# Actuators.net
KiCad netlist of a schematic drawn in Altium Designer
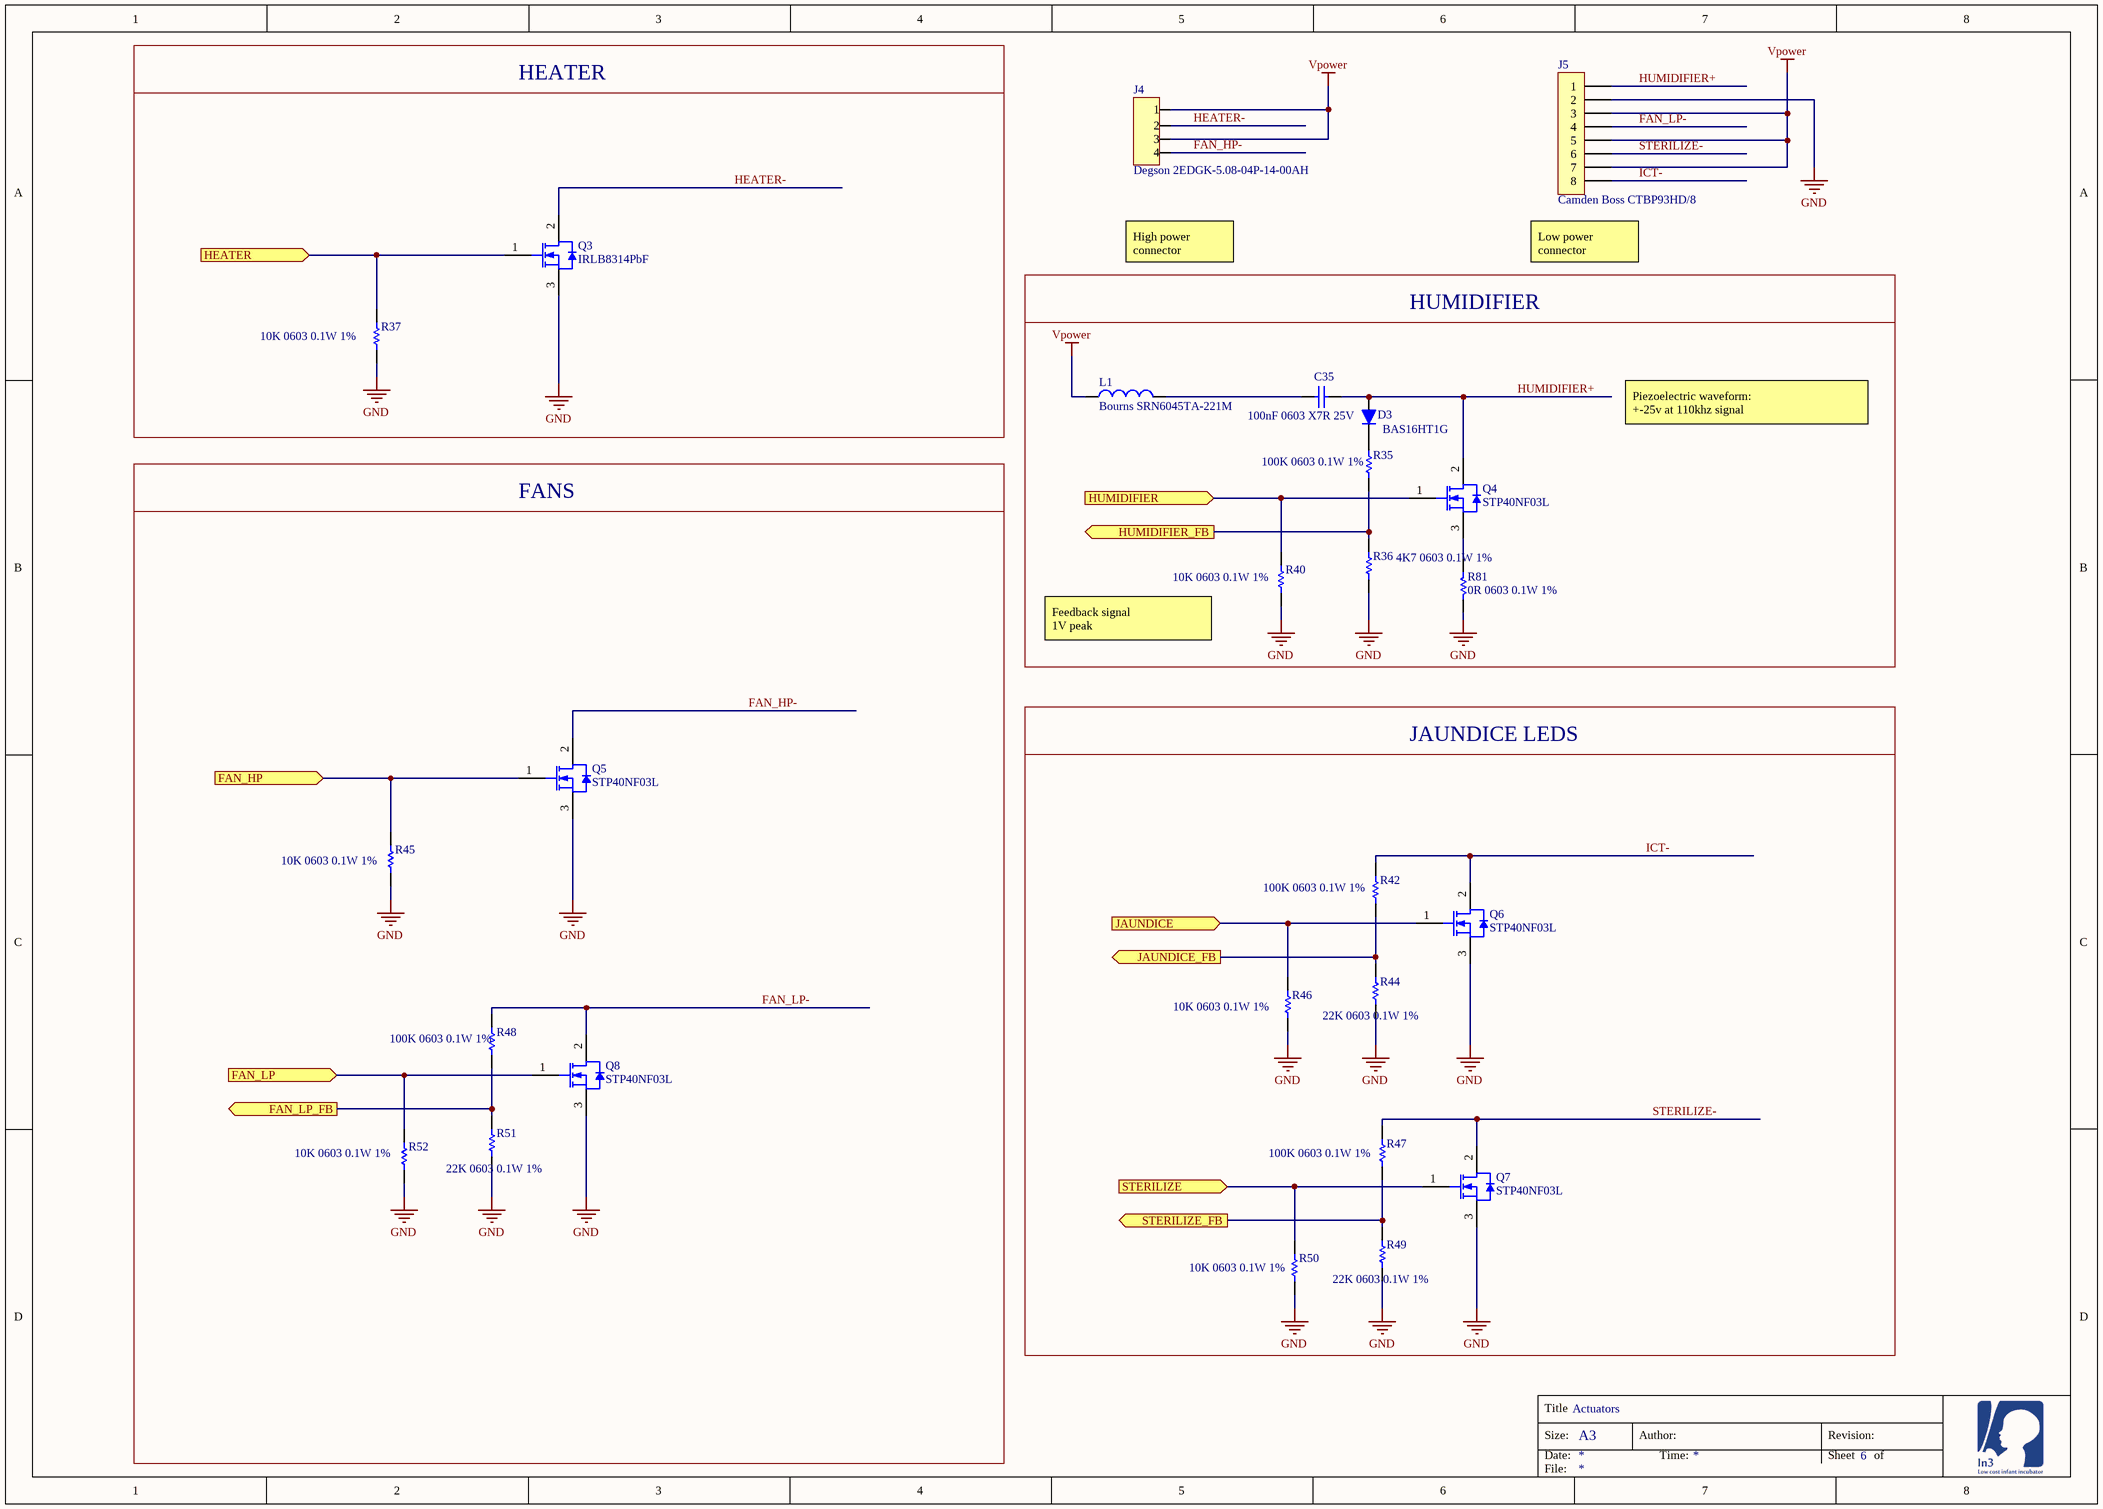
[diagram p0: Actuators.SchDoc]

(export (version "E")
  (design (tool "Eeschema 10.0.6"))
  (components
    (comp (ref "C35")
      (value "100nF 0603 X7R 25V")
      (footprint "CAPC1608X60X35NL10T15")
      (libsource (lib "CommunityVault") (part "CMP-c41a0d2b65641bdd-3"))
    )
    (comp (ref "D3")
      (value "ON Semiconductor BAS16HT1G")
      (footprint "PCB-eawsmpajajexc0e6wrcv-1")
      (description "Diode; Rectifier; Switching; Vr 75VDC; If 200mA; Pkg SOD-323; Vf 1250mV; Trr 6ns; Cj 2pF")
      (fields (field (name "MANUFACTURER PART NUMBER") "BAS16HT1G"))
      (libsource (lib "CommunityVault") (part "CMP-817941-4"))
    )
    (comp (ref "J4")
      (value "Degson 2EDGK-5.08-04P-14-00AH")
      (footprint "PCB-h4cyb3wxd4gf7j132tzl-1")
      (description "Terminal block, 5.08mm 4 Pos, through hole male.")
      (fields (field (name "MANUFACTURER PART NUMBER") "2EDGA-5.08-04P-14-00AH"))
      (libsource (lib "FavoritesLibrary") (part "SYM-0d24c6756598d2e3-1"))
    )
    (comp (ref "J5")
      (value "Camden Boss CTBP93HD/8")
      (footprint "PCB-x5bf0tdd06kg49qqqpah-1")
      (description "3.5mm pluggable terminal block, header, 8P")
      (fields (field (name "MANUFACTURER PART NUMBER") "CTBP93HD/8"))
      (libsource (lib "FavoritesLibrary") (part "SYM-0617cd461937d9d0-1"))
    )
    (comp (ref "L1")
      (value "Bourns SRN6045TA-221M")
      (footprint "PCB-wv16t2tzy3vtnr72ahin-1")
      (fields (field (name "MANUFACTURER PART NUMBER") "SRN6045TA-221M"))
      (libsource (lib "FavoritesLibrary") (part "SYM-d1e61c97cd460e21-1"))
    )
    (comp (ref "Q3")
      (value "IRLB8314PbF")
      (footprint "ONSC-TO-220-3-221A-07")
      (description "MOSFET Transistor, N Channel, 130 A, 30 V, 0.0019 ohm, 10 V, 1.7 V")
      (fields (field (name "MANUFACTURER") "Infineon"))
      (libsource (lib "CommunityVault") (part "CMP-lktjqnj8y0zfb5fwtotb-1"))
    )
    (comp (ref "Q4")
      (value "STP40NF03L")
      (footprint "ONSC-TO-220-3-221A-07")
      (fields
        (field (name "MANUFACTURER") "Infineon")
        (field (name "MANUFACTURER PART NUMBER") "IRLB8314PbF")
      )
      (libsource (lib "CommunityVault") (part "CMP-lktjqnj8y0zfb5fwtotb-1"))
    )
    (comp (ref "Q5")
      (value "STP40NF03L")
      (footprint "ONSC-TO-220-3-221A-07")
      (fields
        (field (name "MANUFACTURER") "Infineon")
        (field (name "MANUFACTURER PART NUMBER") "IRLB8314PbF")
      )
      (libsource (lib "CommunityVault") (part "CMP-lktjqnj8y0zfb5fwtotb-1"))
    )
    (comp (ref "Q6")
      (value "STP40NF03L")
      (footprint "ONSC-TO-220-3-221A-07")
      (fields
        (field (name "MANUFACTURER") "Infineon")
        (field (name "MANUFACTURER PART NUMBER") "IRLB8314PbF")
      )
      (libsource (lib "CommunityVault") (part "CMP-lktjqnj8y0zfb5fwtotb-1"))
    )
    (comp (ref "Q7")
      (value "STP40NF03L")
      (footprint "ONSC-TO-220-3-221A-07")
      (fields
        (field (name "MANUFACTURER") "Infineon")
        (field (name "MANUFACTURER PART NUMBER") "IRLB8314PbF")
      )
      (libsource (lib "CommunityVault") (part "CMP-lktjqnj8y0zfb5fwtotb-1"))
    )
    (comp (ref "Q8")
      (value "STP40NF03L")
      (footprint "ONSC-TO-220-3-221A-07")
      (fields
        (field (name "MANUFACTURER") "Infineon")
        (field (name "MANUFACTURER PART NUMBER") "IRLB8314PbF")
      )
      (libsource (lib "CommunityVault") (part "CMP-lktjqnj8y0zfb5fwtotb-1"))
    )
    (comp (ref "R35")
      (value "100K 0603 0.1W 1%")
      (footprint "RESC1609X55X30ML10T20")
      (fields (field (name "TOLERANCE") "1%"))
      (libsource (lib "CommunityVault") (part "CMP-3655986-6"))
    )
    (comp (ref "R36")
      (value "4K7 0603 0.1W 1%")
      (footprint "RESC1609X55X30ML10T20")
      (fields (field (name "TOLERANCE") "1%"))
      (libsource (lib "CommunityVault") (part "CMP-3655986-6"))
    )
    (comp (ref "R37")
      (value "10K 0603 0.1W 1%")
      (footprint "RESC1609X55X30ML10T20")
      (fields (field (name "TOLERANCE") "1%"))
      (libsource (lib "CommunityVault") (part "CMP-4716590-9"))
    )
    (comp (ref "R40")
      (value "10K 0603 0.1W 1%")
      (footprint "RESC1609X55X30ML10T20")
      (fields (field (name "TOLERANCE") "1%"))
      (libsource (lib "CommunityVault") (part "CMP-4716590-9"))
    )
    (comp (ref "R42")
      (value "100K 0603 0.1W 1%")
      (footprint "RESC1609X55X30ML10T20")
      (fields (field (name "MANUFACTURER PART NUMBER") "CRCW0603100KFKEA"))
      (libsource (lib "CommunityVault") (part "CMP-16231689-7"))
    )
    (comp (ref "R44")
      (value "22K 0603 0.1W 1%")
      (footprint "RESC1609X55X30ML10T20")
      (fields (field (name "TOLERANCE") "1%"))
      (libsource (lib "CommunityVault") (part "CMP-3655986-6"))
    )
    (comp (ref "R45")
      (value "10K 0603 0.1W 1%")
      (footprint "RESC1609X55X30ML10T20")
      (fields (field (name "TOLERANCE") "1%"))
      (libsource (lib "CommunityVault") (part "CMP-4716590-9"))
    )
    (comp (ref "R46")
      (value "10K 0603 0.1W 1%")
      (footprint "RESC1609X55X30ML10T20")
      (fields (field (name "TOLERANCE") "1%"))
      (libsource (lib "CommunityVault") (part "CMP-4716590-9"))
    )
    (comp (ref "R47")
      (value "100K 0603 0.1W 1%")
      (footprint "RESC1609X55X30ML10T20")
      (fields (field (name "MANUFACTURER PART NUMBER") "CRCW0603100KFKEA"))
      (libsource (lib "CommunityVault") (part "CMP-16231689-7"))
    )
    (comp (ref "R48")
      (value "100K 0603 0.1W 1%")
      (footprint "RESC1609X55X30ML10T20")
      (fields (field (name "TOLERANCE") "1%"))
      (libsource (lib "CommunityVault") (part "CMP-3655986-6"))
    )
    (comp (ref "R49")
      (value "22K 0603 0.1W 1%")
      (footprint "RESC1609X55X30ML10T20")
      (fields (field (name "TOLERANCE") "1%"))
      (libsource (lib "CommunityVault") (part "CMP-3655986-6"))
    )
    (comp (ref "R50")
      (value "10K 0603 0.1W 1%")
      (footprint "RESC1609X55X30ML10T20")
      (fields (field (name "TOLERANCE") "1%"))
      (libsource (lib "CommunityVault") (part "CMP-4716590-9"))
    )
    (comp (ref "R51")
      (value "22K 0603 0.1W 1%")
      (footprint "RESC1609X55X30ML10T20")
      (fields (field (name "TOLERANCE") "1%"))
      (libsource (lib "CommunityVault") (part "CMP-4716590-9"))
    )
    (comp (ref "R52")
      (value "10K 0603 0.1W 1%")
      (footprint "RESC1609X55X30ML10T20")
      (fields (field (name "TOLERANCE") "1%"))
      (libsource (lib "CommunityVault") (part "CMP-4716590-9"))
    )
    (comp (ref "R81")
      (value "0R 0603 0.1W 1%")
      (footprint "RESC1609X55X30ML10T20")
      (libsource (lib "CommunityVault") (part "CMP-536b9a7387ce8cac-10"))
    )
  )
  (nets
    (net (code "1") (name "/FAN_HP") (class "Default")
      (node (ref "Q5") (pin "1") (pinfunction "GATE_1") (pintype "passive"))
      (node (ref "R45") (pin "2") (pinfunction "2_2") (pintype "passive"))
    )
    (net (code "2") (name "/FAN_HP-") (class "Default")
      (node (ref "J4") (pin "4") (pinfunction "4_4") (pintype "passive"))
      (node (ref "Q5") (pin "2") (pinfunction "DRAIN_2") (pintype "passive"))
    )
    (net (code "3") (name "/FAN_LP") (class "Default")
      (node (ref "Q8") (pin "1") (pinfunction "GATE_1") (pintype "passive"))
      (node (ref "R52") (pin "2") (pinfunction "2_2") (pintype "passive"))
    )
    (net (code "4") (name "/FAN_LP-") (class "Default")
      (node (ref "J5") (pin "4") (pinfunction "4_4") (pintype "passive"))
      (node (ref "Q8") (pin "2") (pinfunction "DRAIN_2") (pintype "passive"))
      (node (ref "R48") (pin "1") (pinfunction "1_1") (pintype "passive"))
    )
    (net (code "5") (name "/FAN_LP_FB") (class "Default")
      (node (ref "R48") (pin "2") (pinfunction "2_2") (pintype "passive"))
      (node (ref "R51") (pin "2") (pinfunction "2_2") (pintype "passive"))
    )
    (net (code "6") (name "/HEATER") (class "Default")
      (node (ref "Q3") (pin "1") (pinfunction "GATE_1") (pintype "passive"))
      (node (ref "R37") (pin "2") (pinfunction "2_2") (pintype "passive"))
    )
    (net (code "7") (name "/HEATER-") (class "Default")
      (node (ref "J4") (pin "2") (pinfunction "2_2") (pintype "passive"))
      (node (ref "Q3") (pin "2") (pinfunction "DRAIN_2") (pintype "passive"))
    )
    (net (code "8") (name "/HUMIDIFIER") (class "Default")
      (node (ref "Q4") (pin "1") (pinfunction "GATE_1") (pintype "passive"))
      (node (ref "R40") (pin "2") (pinfunction "2_2") (pintype "passive"))
    )
    (net (code "9") (name "/HUMIDIFIER+") (class "Default")
      (node (ref "C35") (pin "1") (pinfunction "1_1") (pintype "passive"))
      (node (ref "D3") (pin "2") (pinfunction "A_2") (pintype "passive"))
      (node (ref "J5") (pin "1") (pinfunction "1_1") (pintype "passive"))
      (node (ref "Q4") (pin "2") (pinfunction "DRAIN_2") (pintype "passive"))
    )
    (net (code "10") (name "/HUMIDIFIER_FB") (class "Default")
      (node (ref "R35") (pin "2") (pinfunction "2_2") (pintype "passive"))
      (node (ref "R36") (pin "2") (pinfunction "2_2") (pintype "passive"))
    )
    (net (code "11") (name "/ICT-") (class "Default")
      (node (ref "J5") (pin "8") (pinfunction "8_8") (pintype "passive"))
      (node (ref "Q6") (pin "2") (pinfunction "DRAIN_2") (pintype "passive"))
      (node (ref "R42") (pin "2") (pinfunction "2_2") (pintype "passive"))
    )
    (net (code "12") (name "/JAUNDICE") (class "Default")
      (node (ref "Q6") (pin "1") (pinfunction "GATE_1") (pintype "passive"))
      (node (ref "R46") (pin "2") (pinfunction "2_2") (pintype "passive"))
    )
    (net (code "13") (name "/JAUNDICE_FB") (class "Default")
      (node (ref "R42") (pin "1") (pinfunction "1_1") (pintype "passive"))
      (node (ref "R44") (pin "1") (pinfunction "1_1") (pintype "passive"))
    )
    (net (code "14") (name "/STERILIZE") (class "Default")
      (node (ref "Q7") (pin "1") (pinfunction "GATE_1") (pintype "passive"))
      (node (ref "R50") (pin "2") (pinfunction "2_2") (pintype "passive"))
    )
    (net (code "15") (name "/STERILIZE-") (class "Default")
      (node (ref "J5") (pin "6") (pinfunction "6_6") (pintype "passive"))
      (node (ref "Q7") (pin "2") (pinfunction "DRAIN_2") (pintype "passive"))
      (node (ref "R47") (pin "2") (pinfunction "2_2") (pintype "passive"))
    )
    (net (code "16") (name "/STERILIZE_FB") (class "Default")
      (node (ref "R47") (pin "1") (pinfunction "1_1") (pintype "passive"))
      (node (ref "R49") (pin "1") (pinfunction "1_1") (pintype "passive"))
    )
    (net (code "17") (name "GND") (class "Default")
      (node (ref "J5") (pin "2") (pinfunction "2_2") (pintype "passive"))
      (node (ref "Q3") (pin "3") (pinfunction "SOURCE_3") (pintype "passive"))
      (node (ref "Q5") (pin "3") (pinfunction "SOURCE_3") (pintype "passive"))
      (node (ref "Q6") (pin "3") (pinfunction "SOURCE_3") (pintype "passive"))
      (node (ref "Q7") (pin "3") (pinfunction "SOURCE_3") (pintype "passive"))
      (node (ref "Q8") (pin "3") (pinfunction "SOURCE_3") (pintype "passive"))
      (node (ref "R36") (pin "1") (pinfunction "1_1") (pintype "passive"))
      (node (ref "R37") (pin "1") (pinfunction "1_1") (pintype "passive"))
      (node (ref "R40") (pin "1") (pinfunction "1_1") (pintype "passive"))
      (node (ref "R44") (pin "2") (pinfunction "2_2") (pintype "passive"))
      (node (ref "R45") (pin "1") (pinfunction "1_1") (pintype "passive"))
      (node (ref "R46") (pin "1") (pinfunction "1_1") (pintype "passive"))
      (node (ref "R49") (pin "2") (pinfunction "2_2") (pintype "passive"))
      (node (ref "R50") (pin "1") (pinfunction "1_1") (pintype "passive"))
      (node (ref "R51") (pin "1") (pinfunction "1_1") (pintype "passive"))
      (node (ref "R52") (pin "1") (pinfunction "1_1") (pintype "passive"))
      (node (ref "R81") (pin "2") (pinfunction "2_2") (pintype "passive"))
    )
    (net (code "18") (name "Net-(C35-Pad2)") (class "Default")
      (node (ref "C35") (pin "2") (pinfunction "2_2") (pintype "passive"))
      (node (ref "L1") (pin "2") (pinfunction "2_2") (pintype "passive"))
    )
    (net (code "19") (name "Net-(D3-K)") (class "Default")
      (node (ref "D3") (pin "1") (pinfunction "K_1") (pintype "passive"))
      (node (ref "R35") (pin "1") (pinfunction "1_1") (pintype "passive"))
    )
    (net (code "20") (name "Net-(Q4-SOURCE)") (class "Default")
      (node (ref "Q4") (pin "3") (pinfunction "SOURCE_3") (pintype "passive"))
      (node (ref "R81") (pin "1") (pinfunction "1_1") (pintype "passive"))
    )
    (net (code "21") (name "Vpower") (class "Default")
      (node (ref "J4") (pin "1") (pinfunction "1_1") (pintype "passive"))
      (node (ref "J4") (pin "3") (pinfunction "3_3") (pintype "passive"))
      (node (ref "J5") (pin "3") (pinfunction "3_3") (pintype "passive"))
      (node (ref "J5") (pin "5") (pinfunction "5_5") (pintype "passive"))
      (node (ref "J5") (pin "7") (pinfunction "7_7") (pintype "passive"))
      (node (ref "L1") (pin "1") (pinfunction "1_1") (pintype "passive"))
    )
  )
)
